# Sheet2.net
KiCad netlist of a schematic drawn in Altium Designer
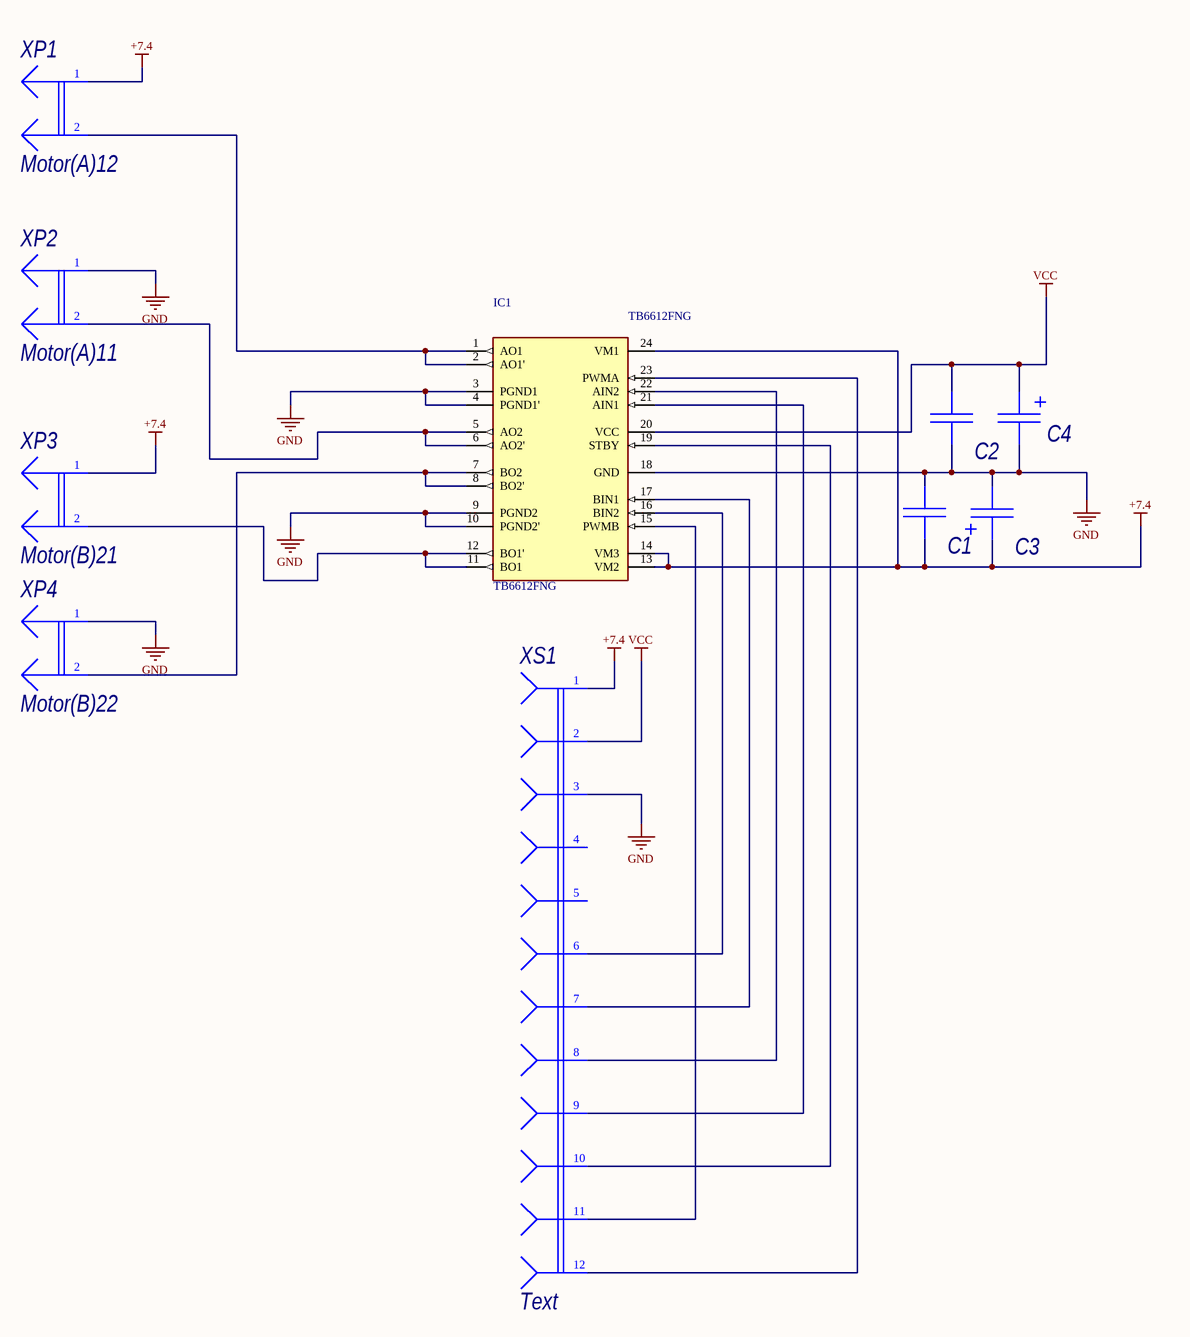
[diagram p0: Sheet2.SchDoc]

(export (version "E")
  (design (tool "Eeschema 10.0.6"))
  (components
    (comp (ref "C1")
      (value "Capacitor")
      (footprint "C0603")
      (description "0.1 uF")
      (fields
        (field (name "PART NUMBER") "GRM188R71C104KA01D")
        (field (name "VOLTAGE") "16V")
        (field (name "PUBLISHER") "Andrew Danich")
      )
      (libsource (lib "Lib_IMP_GOST") (part "Capacitor"))
    )
    (comp (ref "C2")
      (value "Capacitor")
      (footprint "C0603")
      (description "0.1 uF")
      (fields
        (field (name "PART NUMBER") "GRM188R71C104KA01D")
        (field (name "VOLTAGE") "16V")
        (field (name "PUBLISHER") "Andrew Danich")
      )
      (libsource (lib "Lib_IMP_GOST") (part "Capacitor"))
    )
    (comp (ref "C3")
      (value "Capacitor-T")
      (footprint "C3216-p")
      (description "10 uF")
      (fields
        (field (name "PART NUMBER") "T491A106K006AT")
        (field (name "VOLTAGE") "6.3V")
        (field (name "PUBLISHER") "Andrew Danich")
      )
      (libsource (lib "Lib_IMP_GOST") (part "Capacitor-T"))
    )
    (comp (ref "C4")
      (value "Capacitor-T")
      (footprint "C3216-p")
      (description "10 uF")
      (fields
        (field (name "PART NUMBER") "T491A106K006AT")
        (field (name "VOLTAGE") "6.3V")
        (field (name "PUBLISHER") "Andrew Danich")
      )
      (libsource (lib "Lib_IMP_GOST") (part "Capacitor-T"))
    )
    (comp (ref "IC1")
      (value "TB6612FNG")
      (footprint "SSOP24")
      (description "Motor Driver Power MOSFET Parallel 24-SSOP")
      (fields (field (name "MF") "Toshiba"))
      (libsource (lib "TB6612FNG") (part "TB6612FNG"))
    )
    (comp (ref "XP1")
      (value "Motor(A)12")
      (footprint "PLS-2")
      (fields (field (name "PART NUMBER") "PLS-2") (field (name "PUBLISHER") "Andrew Danich"))
      (libsource (lib "Lib_IMP_GOST") (part "Con-2-M"))
    )
    (comp (ref "XP2")
      (value "Motor(A)11")
      (footprint "PLS-2")
      (fields (field (name "PART NUMBER") "PLS-2") (field (name "PUBLISHER") "Andrew Danich"))
      (libsource (lib "Lib_IMP_GOST") (part "Con-2-M"))
    )
    (comp (ref "XP3")
      (value "Motor(B)21")
      (footprint "PLS-2")
      (fields (field (name "PART NUMBER") "PLS-2") (field (name "PUBLISHER") "Andrew Danich"))
      (libsource (lib "Lib_IMP_GOST") (part "Con-2-M"))
    )
    (comp (ref "XP4")
      (value "Motor(B)22")
      (footprint "PLS-2")
      (fields (field (name "PART NUMBER") "PLS-2") (field (name "PUBLISHER") "Andrew Danich"))
      (libsource (lib "Lib_IMP_GOST") (part "Con-2-M"))
    )
    (comp (ref "XS1")
      (value "Text")
      (footprint "PBS-12")
      (fields (field (name "PART NUMBER") "PBS-12") (field (name "PUBLISHER") "Andrew Danich"))
      (libsource (lib "Lib_IMP_GOST") (part "Con-12-F"))
    )
  )
  (nets
    (net (code "1") (name "+7.4") (class "Default")
      (node (ref "C1") (pin "1") (pinfunction "1_1") (pintype "passive"))
      (node (ref "C3") (pin "1") (pinfunction "1_1") (pintype "passive"))
      (node (ref "IC1") (pin "13") (pinfunction "VM2_13") (pintype "power_in"))
      (node (ref "IC1") (pin "14") (pinfunction "VM3_14") (pintype "power_in"))
      (node (ref "IC1") (pin "24") (pinfunction "VM1_24") (pintype "power_in"))
      (node (ref "XP1") (pin "1") (pintype "passive"))
      (node (ref "XP3") (pin "1") (pintype "passive"))
      (node (ref "XS1") (pin "1") (pintype "passive"))
    )
    (net (code "2") (name "GND") (class "Default")
      (node (ref "C1") (pin "2") (pinfunction "2_2") (pintype "passive"))
      (node (ref "C2") (pin "1") (pinfunction "1_1") (pintype "passive"))
      (node (ref "C3") (pin "2") (pinfunction "2_2") (pintype "passive"))
      (node (ref "C4") (pin "2") (pinfunction "2_2") (pintype "passive"))
      (node (ref "IC1") (pin "10") (pinfunction "PGND2'_10") (pintype "power_in"))
      (node (ref "IC1") (pin "18") (pinfunction "GND_18") (pintype "power_in"))
      (node (ref "IC1") (pin "3") (pinfunction "PGND1_3") (pintype "power_in"))
      (node (ref "IC1") (pin "4") (pinfunction "PGND1'_4") (pintype "power_in"))
      (node (ref "IC1") (pin "9") (pinfunction "PGND2_9") (pintype "power_in"))
      (node (ref "XP2") (pin "1") (pintype "passive"))
      (node (ref "XP4") (pin "1") (pintype "passive"))
      (node (ref "XS1") (pin "3") (pintype "passive"))
    )
    (net (code "3") (name "Net-(IC1-AIN1)") (class "Default")
      (node (ref "IC1") (pin "21") (pinfunction "AIN1_21") (pintype "input"))
      (node (ref "XS1") (pin "9") (pintype "passive"))
    )
    (net (code "4") (name "Net-(IC1-AIN2)") (class "Default")
      (node (ref "IC1") (pin "22") (pinfunction "AIN2_22") (pintype "input"))
      (node (ref "XS1") (pin "8") (pintype "passive"))
    )
    (net (code "5") (name "Net-(IC1-AO1')") (class "Default")
      (node (ref "IC1") (pin "1") (pinfunction "AO1_1") (pintype "output"))
      (node (ref "IC1") (pin "2") (pinfunction "AO1'_2") (pintype "output"))
      (node (ref "XP1") (pin "2") (pintype "passive"))
    )
    (net (code "6") (name "Net-(IC1-AO2')") (class "Default")
      (node (ref "IC1") (pin "5") (pinfunction "AO2_5") (pintype "output"))
      (node (ref "IC1") (pin "6") (pinfunction "AO2'_6") (pintype "output"))
      (node (ref "XP2") (pin "2") (pintype "passive"))
    )
    (net (code "7") (name "Net-(IC1-BIN1)") (class "Default")
      (node (ref "IC1") (pin "17") (pinfunction "BIN1_17") (pintype "input"))
      (node (ref "XS1") (pin "7") (pintype "passive"))
    )
    (net (code "8") (name "Net-(IC1-BIN2)") (class "Default")
      (node (ref "IC1") (pin "16") (pinfunction "BIN2_16") (pintype "input"))
      (node (ref "XS1") (pin "6") (pintype "passive"))
    )
    (net (code "9") (name "Net-(IC1-BO1')") (class "Default")
      (node (ref "IC1") (pin "11") (pinfunction "BO1_11") (pintype "output"))
      (node (ref "IC1") (pin "12") (pinfunction "BO1'_12") (pintype "output"))
      (node (ref "XP3") (pin "2") (pintype "passive"))
    )
    (net (code "10") (name "Net-(IC1-BO2')") (class "Default")
      (node (ref "IC1") (pin "7") (pinfunction "BO2_7") (pintype "output"))
      (node (ref "IC1") (pin "8") (pinfunction "BO2'_8") (pintype "output"))
      (node (ref "XP4") (pin "2") (pintype "passive"))
    )
    (net (code "11") (name "Net-(IC1-PWMA)") (class "Default")
      (node (ref "IC1") (pin "23") (pinfunction "PWMA_23") (pintype "input"))
      (node (ref "XS1") (pin "12") (pintype "passive"))
    )
    (net (code "12") (name "Net-(IC1-PWMB)") (class "Default")
      (node (ref "IC1") (pin "15") (pinfunction "PWMB_15") (pintype "input"))
      (node (ref "XS1") (pin "11") (pintype "passive"))
    )
    (net (code "13") (name "Net-(IC1-STBY)") (class "Default")
      (node (ref "IC1") (pin "19") (pinfunction "STBY_19") (pintype "input"))
      (node (ref "XS1") (pin "10") (pintype "passive"))
    )
    (net (code "14") (name "VCC") (class "Default")
      (node (ref "C2") (pin "2") (pinfunction "2_2") (pintype "passive"))
      (node (ref "C4") (pin "1") (pinfunction "1_1") (pintype "passive"))
      (node (ref "IC1") (pin "20") (pinfunction "VCC_20") (pintype "power_in"))
      (node (ref "XS1") (pin "2") (pintype "passive"))
    )
    (net (code "15") (name "unconnected-(XS1-Pad4)") (class "Default")
      (node (ref "XS1") (pin "4") (pintype "passive"))
    )
    (net (code "16") (name "unconnected-(XS1-Pad5)") (class "Default")
      (node (ref "XS1") (pin "5") (pintype "passive"))
    )
  )
)
